# V-USB_Volume_Control_T2313_V1_1_60mm_x_6.net
KiCad netlist of a schematic drawn in EAGLE
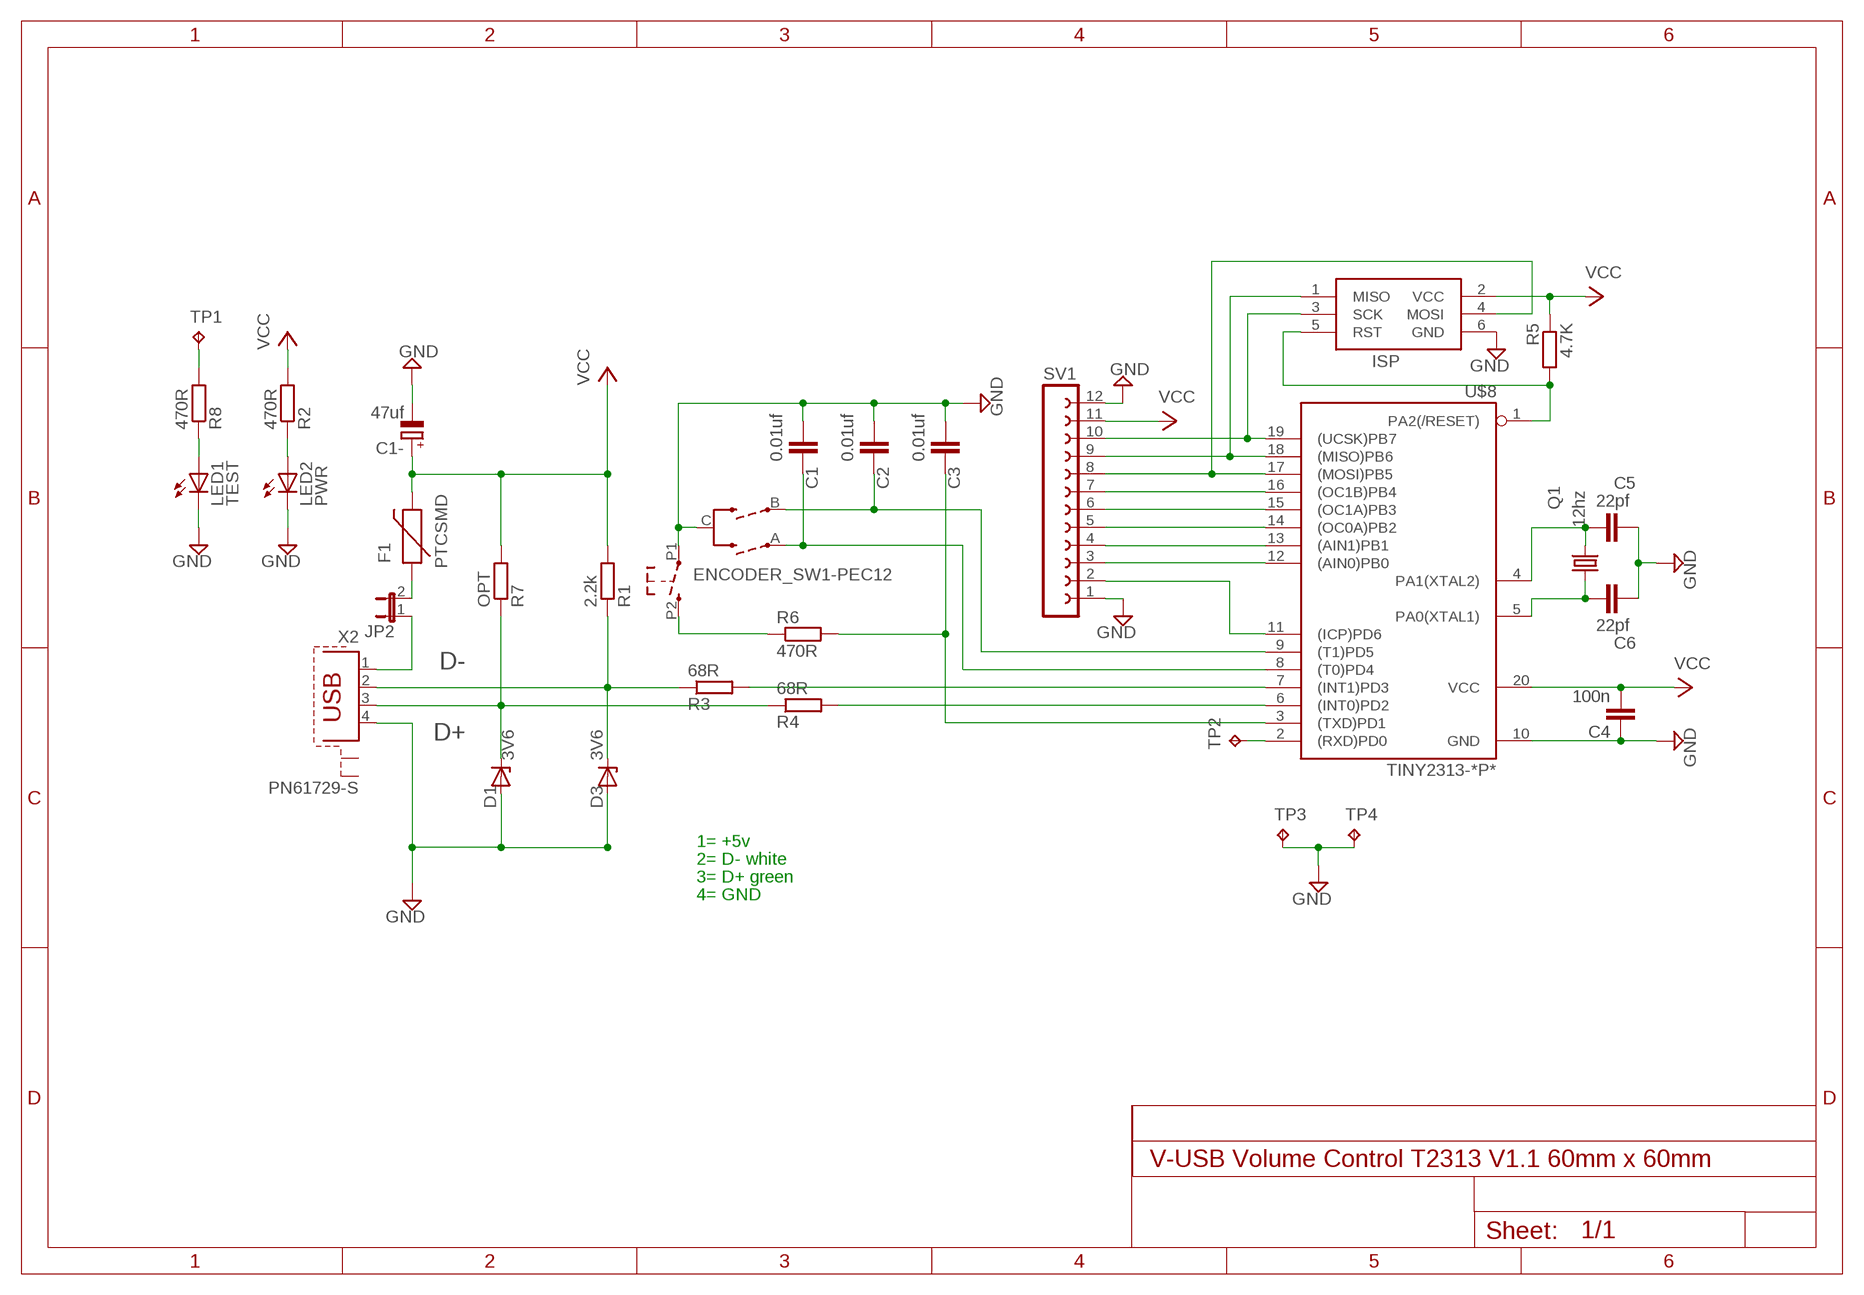
[diagram p0: schematic, sheet 1]

(export (version "E")
  (design (tool "Eeschema 10.0.6"))
  (components
    (comp (ref "C1")
      (value "0.01uf")
      (footprint "eagle-import:C5B2.5")
      (libsource (lib "eagle-import") (part "C5/2.5"))
    )
    (comp (ref "C1-")
      (value "47uf")
      (footprint "eagle-import:E2,5-6")
      (libsource (lib "eagle-import") (part "CPOL-EUE2.5-6"))
    )
    (comp (ref "C2")
      (value "0.01uf")
      (footprint "eagle-import:C5B2.5")
      (libsource (lib "eagle-import") (part "C5/2.5"))
    )
    (comp (ref "C3")
      (value "0.01uf")
      (footprint "eagle-import:C5B2.5")
      (libsource (lib "eagle-import") (part "C5/2.5"))
    )
    (comp (ref "C4")
      (value "100n")
      (footprint "eagle-import:C5B2.5")
      (libsource (lib "eagle-import") (part "C5/2.5"))
    )
    (comp (ref "C5")
      (value "22pf")
      (footprint "eagle-import:C2.5-2")
      (libsource (lib "eagle-import") (part "C2.5/2"))
    )
    (comp (ref "C6")
      (value "22pf")
      (footprint "eagle-import:C2.5-2")
      (libsource (lib "eagle-import") (part "C2.5/2"))
    )
    (comp (ref "D1")
      (value "3V6")
      (footprint "eagle-import:DO34Z7")
      (libsource (lib "eagle-import") (part "ZENER-DIODEDO34-7"))
    )
    (comp (ref "D3")
      (value "3V6")
      (footprint "eagle-import:DO34Z7")
      (libsource (lib "eagle-import") (part "ZENER-DIODEDO34-7"))
    )
    (comp (ref "F1")
      (value "PTCSMD")
      (footprint "eagle-import:PTC-1206")
      (libsource (lib "eagle-import") (part "PTCSMD"))
    )
    (comp (ref "ISP")
      (value "AVRISP-6")
      (footprint "eagle-import:AVRISP")
      (libsource (lib "eagle-import") (part "AVRISP-6"))
    )
    (comp (ref "JP2")
      (value "JP1E")
      (footprint "eagle-import:JP1")
      (libsource (lib "eagle-import") (part "JP1E"))
    )
    (comp (ref "LED1")
      (value "TEST")
      (footprint "eagle-import:LED3MM")
      (libsource (lib "eagle-import") (part "LED3MM"))
    )
    (comp (ref "LED2")
      (value "PWR")
      (footprint "eagle-import:LED3MM")
      (libsource (lib "eagle-import") (part "LED3MM"))
    )
    (comp (ref "Q1")
      (value "12hz")
      (footprint "eagle-import:HC49_S")
      (libsource (lib "eagle-import") (part "CRYSTALHC49S"))
    )
    (comp (ref "R1")
      (value "2.2k")
      (footprint "eagle-import:0207_10")
      (libsource (lib "eagle-import") (part "R-EU_0207/10"))
    )
    (comp (ref "R2")
      (value "470R")
      (footprint "eagle-import:0204_7")
      (libsource (lib "eagle-import") (part "R-EU_0204/7"))
    )
    (comp (ref "R3")
      (value "68R")
      (footprint "eagle-import:0207_10")
      (libsource (lib "eagle-import") (part "R-EU_0207/10"))
    )
    (comp (ref "R4")
      (value "68R")
      (footprint "eagle-import:0207_10")
      (libsource (lib "eagle-import") (part "R-EU_0207/10"))
    )
    (comp (ref "R5")
      (value "4.7K")
      (footprint "eagle-import:0204_7")
      (libsource (lib "eagle-import") (part "R-EU_0204/7"))
    )
    (comp (ref "R6")
      (value "470R")
      (footprint "eagle-import:0204_7")
      (libsource (lib "eagle-import") (part "R-EU_0204/7"))
    )
    (comp (ref "R7")
      (value "OPT")
      (footprint "eagle-import:0207_10")
      (libsource (lib "eagle-import") (part "R-EU_0207/10"))
    )
    (comp (ref "R8")
      (value "470R")
      (footprint "eagle-import:0207_10")
      (libsource (lib "eagle-import") (part "R-EU_0207/10"))
    )
    (comp (ref "SV1")
      (value "FE12-1")
      (footprint "eagle-import:FE12")
      (libsource (lib "eagle-import") (part "FE12-1"))
    )
    (comp (ref "SW3")
      (value "ENCODER_SW1-PEC12")
      (footprint "eagle-import:PEC12_INCREMENTAL_ENCODER")
      (libsource (lib "eagle-import") (part "ENCODER_SW1-PEC12"))
    )
    (comp (ref "TP1")
      (value "TPPAD1-13")
      (footprint "eagle-import:P1-13")
      (libsource (lib "eagle-import") (part "TPPAD1-13"))
    )
    (comp (ref "TP2")
      (value "TPPAD1-13")
      (footprint "eagle-import:P1-13")
      (libsource (lib "eagle-import") (part "TPPAD1-13"))
    )
    (comp (ref "TP3")
      (value "TPPAD1-20Y")
      (footprint "eagle-import:P1-20Y")
      (libsource (lib "eagle-import") (part "TPPAD1-20Y"))
    )
    (comp (ref "TP4")
      (value "TPPAD1-20Y")
      (footprint "eagle-import:P1-20Y")
      (libsource (lib "eagle-import") (part "TPPAD1-20Y"))
    )
    (comp (ref "U$8")
      (value "TINY2313-*P*")
      (footprint "eagle-import:DIL20")
      (libsource (lib "eagle-import") (part "TINY2313-P"))
    )
    (comp (ref "X2")
      (value "PN61729-S")
      (footprint "eagle-import:PN61729-S")
      (libsource (lib "eagle-import") (part "PN61729-S"))
    )
  )
  (nets
    (net (code "1") (name "/D+") (class "Default")
      (node (ref "D1") (pin "C") (pinfunction "C_C") (pintype "passive"))
      (node (ref "R4") (pin "1") (pinfunction "1_1") (pintype "passive"))
      (node (ref "R7") (pin "1") (pinfunction "1_1") (pintype "passive"))
      (node (ref "X2") (pin "3") (pinfunction "3_3") (pintype "passive"))
    )
    (net (code "2") (name "/D-") (class "Default")
      (node (ref "D3") (pin "C") (pinfunction "C_C") (pintype "passive"))
      (node (ref "R1") (pin "1") (pinfunction "1_1") (pintype "passive"))
      (node (ref "R3") (pin "1") (pinfunction "1_1") (pintype "passive"))
      (node (ref "X2") (pin "2") (pinfunction "2_2") (pintype "passive"))
    )
    (net (code "3") (name "GND") (class "Default")
      (node (ref "C1") (pin "1") (pinfunction "1_1") (pintype "passive"))
      (node (ref "C1-") (pin "-") (pinfunction "-_-") (pintype "passive"))
      (node (ref "C2") (pin "1") (pinfunction "1_1") (pintype "passive"))
      (node (ref "C3") (pin "1") (pinfunction "1_1") (pintype "passive"))
      (node (ref "C4") (pin "1") (pinfunction "1_1") (pintype "passive"))
      (node (ref "C5") (pin "2") (pinfunction "2_2") (pintype "passive"))
      (node (ref "C6") (pin "2") (pinfunction "2_2") (pintype "passive"))
      (node (ref "D1") (pin "A") (pinfunction "A_A") (pintype "passive"))
      (node (ref "D3") (pin "A") (pinfunction "A_A") (pintype "passive"))
      (node (ref "ISP") (pin "6") (pinfunction "GND_6") (pintype "power_in"))
      (node (ref "LED1") (pin "K") (pinfunction "C_K") (pintype "passive"))
      (node (ref "LED2") (pin "K") (pinfunction "C_K") (pintype "passive"))
      (node (ref "SV1") (pin "1") (pinfunction "1_1") (pintype "passive"))
      (node (ref "SV1") (pin "12") (pinfunction "12_12") (pintype "passive"))
      (node (ref "SW3") (pin "C") (pinfunction "C_C") (pintype "passive"))
      (node (ref "SW3") (pin "P1") (pinfunction "1_P1") (pintype "passive"))
      (node (ref "TP3") (pin "TP") (pinfunction "TP_TP") (pintype "input"))
      (node (ref "TP4") (pin "TP") (pinfunction "TP_TP") (pintype "input"))
      (node (ref "U$8") (pin "10") (pinfunction "GND_10") (pintype "power_in"))
      (node (ref "X2") (pin "4") (pinfunction "4_4") (pintype "passive"))
    )
    (net (code "4") (name "Net-(F1-Pad1)") (class "Default")
      (node (ref "F1") (pin "1") (pinfunction "1_1") (pintype "bidirectional"))
      (node (ref "JP2") (pin "2") (pinfunction "2_2") (pintype "passive"))
    )
    (net (code "5") (name "Net-(ISP-MISO)") (class "Default")
      (node (ref "ISP") (pin "1") (pinfunction "MISO_1") (pintype "input"))
      (node (ref "SV1") (pin "9") (pinfunction "9_9") (pintype "passive"))
      (node (ref "U$8") (pin "18") (pinfunction "(MISO)PB6_18") (pintype "bidirectional"))
    )
    (net (code "6") (name "Net-(ISP-MOSI)") (class "Default")
      (node (ref "ISP") (pin "4") (pinfunction "MOSI_4") (pintype "output"))
      (node (ref "SV1") (pin "8") (pinfunction "8_8") (pintype "passive"))
      (node (ref "U$8") (pin "17") (pinfunction "(MOSI)PB5_17") (pintype "bidirectional"))
    )
    (net (code "7") (name "Net-(ISP-RST)") (class "Default")
      (node (ref "ISP") (pin "5") (pinfunction "RST_5") (pintype "output"))
      (node (ref "R5") (pin "2") (pinfunction "2_2") (pintype "passive"))
      (node (ref "U$8") (pin "1") (pinfunction "PA2(/RESET)_1") (pintype "input"))
    )
    (net (code "8") (name "Net-(ISP-SCK)") (class "Default")
      (node (ref "ISP") (pin "3") (pinfunction "SCK_3") (pintype "output"))
      (node (ref "SV1") (pin "10") (pinfunction "10_10") (pintype "passive"))
      (node (ref "U$8") (pin "19") (pinfunction "(UCSK)PB7_19") (pintype "bidirectional"))
    )
    (net (code "9") (name "Net-(JP2-Pad1)") (class "Default")
      (node (ref "JP2") (pin "1") (pinfunction "1_1") (pintype "passive"))
      (node (ref "X2") (pin "1") (pinfunction "1_1") (pintype "passive"))
    )
    (net (code "10") (name "Net-(LED1-PadA)") (class "Default")
      (node (ref "LED1") (pin "A") (pinfunction "A_A") (pintype "passive"))
      (node (ref "R8") (pin "1") (pinfunction "1_1") (pintype "passive"))
    )
    (net (code "11") (name "Net-(LED2-PadA)") (class "Default")
      (node (ref "LED2") (pin "A") (pinfunction "A_A") (pintype "passive"))
      (node (ref "R2") (pin "1") (pinfunction "1_1") (pintype "passive"))
    )
    (net (code "12") (name "Net-(R8-Pad2)") (class "Default")
      (node (ref "R8") (pin "2") (pinfunction "2_2") (pintype "passive"))
      (node (ref "TP1") (pin "TP") (pinfunction "TP_TP") (pintype "input"))
    )
    (net (code "13") (name "Net-(SW3B-2)") (class "Default")
      (node (ref "R6") (pin "1") (pinfunction "1_1") (pintype "passive"))
      (node (ref "SW3") (pin "P2") (pinfunction "2_P2") (pintype "passive"))
    )
    (net (code "14") (name "Net-(U$8-(AIN0)PB0)") (class "Default")
      (node (ref "SV1") (pin "3") (pinfunction "3_3") (pintype "passive"))
      (node (ref "U$8") (pin "12") (pinfunction "(AIN0)PB0_12") (pintype "bidirectional"))
    )
    (net (code "15") (name "Net-(U$8-(AIN1)PB1)") (class "Default")
      (node (ref "SV1") (pin "4") (pinfunction "4_4") (pintype "passive"))
      (node (ref "U$8") (pin "13") (pinfunction "(AIN1)PB1_13") (pintype "bidirectional"))
    )
    (net (code "16") (name "Net-(U$8-(ICP)PD6)") (class "Default")
      (node (ref "SV1") (pin "2") (pinfunction "2_2") (pintype "passive"))
      (node (ref "U$8") (pin "11") (pinfunction "(ICP)PD6_11") (pintype "bidirectional"))
    )
    (net (code "17") (name "Net-(U$8-(INT0)PD2)") (class "Default")
      (node (ref "R4") (pin "2") (pinfunction "2_2") (pintype "passive"))
      (node (ref "U$8") (pin "6") (pinfunction "(INT0)PD2_6") (pintype "bidirectional"))
    )
    (net (code "18") (name "Net-(U$8-(INT1)PD3)") (class "Default")
      (node (ref "R3") (pin "2") (pinfunction "2_2") (pintype "passive"))
      (node (ref "U$8") (pin "7") (pinfunction "(INT1)PD3_7") (pintype "bidirectional"))
    )
    (net (code "19") (name "Net-(U$8-(OC0A)PB2)") (class "Default")
      (node (ref "SV1") (pin "5") (pinfunction "5_5") (pintype "passive"))
      (node (ref "U$8") (pin "14") (pinfunction "(OC0A)PB2_14") (pintype "bidirectional"))
    )
    (net (code "20") (name "Net-(U$8-(OC1A)PB3)") (class "Default")
      (node (ref "SV1") (pin "6") (pinfunction "6_6") (pintype "passive"))
      (node (ref "U$8") (pin "15") (pinfunction "(OC1A)PB3_15") (pintype "bidirectional"))
    )
    (net (code "21") (name "Net-(U$8-(OC1B)PB4)") (class "Default")
      (node (ref "SV1") (pin "7") (pinfunction "7_7") (pintype "passive"))
      (node (ref "U$8") (pin "16") (pinfunction "(OC1B)PB4_16") (pintype "bidirectional"))
    )
    (net (code "22") (name "Net-(U$8-(RXD)PD0)") (class "Default")
      (node (ref "TP2") (pin "TP") (pinfunction "TP_TP") (pintype "input"))
      (node (ref "U$8") (pin "2") (pinfunction "(RXD)PD0_2") (pintype "bidirectional"))
    )
    (net (code "23") (name "Net-(U$8-(T0)PD4)") (class "Default")
      (node (ref "C1") (pin "2") (pinfunction "2_2") (pintype "passive"))
      (node (ref "SW3") (pin "A") (pinfunction "A_A") (pintype "passive"))
      (node (ref "U$8") (pin "8") (pinfunction "(T0)PD4_8") (pintype "bidirectional"))
    )
    (net (code "24") (name "Net-(U$8-(T1)PD5)") (class "Default")
      (node (ref "C2") (pin "2") (pinfunction "2_2") (pintype "passive"))
      (node (ref "SW3") (pin "B") (pinfunction "B_B") (pintype "passive"))
      (node (ref "U$8") (pin "9") (pinfunction "(T1)PD5_9") (pintype "bidirectional"))
    )
    (net (code "25") (name "Net-(U$8-(TXD)PD1)") (class "Default")
      (node (ref "C3") (pin "2") (pinfunction "2_2") (pintype "passive"))
      (node (ref "R6") (pin "2") (pinfunction "2_2") (pintype "passive"))
      (node (ref "U$8") (pin "3") (pinfunction "(TXD)PD1_3") (pintype "bidirectional"))
    )
    (net (code "26") (name "Net-(U$8-PA0(XTAL1))") (class "Default")
      (node (ref "C6") (pin "1") (pinfunction "1_1") (pintype "passive"))
      (node (ref "Q1") (pin "1") (pinfunction "1_1") (pintype "passive"))
      (node (ref "U$8") (pin "5") (pinfunction "PA0(XTAL1)_5") (pintype "bidirectional"))
    )
    (net (code "27") (name "Net-(U$8-PA1(XTAL2))") (class "Default")
      (node (ref "C5") (pin "1") (pinfunction "1_1") (pintype "passive"))
      (node (ref "Q1") (pin "2") (pinfunction "2_2") (pintype "passive"))
      (node (ref "U$8") (pin "4") (pinfunction "PA1(XTAL2)_4") (pintype "bidirectional"))
    )
    (net (code "28") (name "VCC") (class "Default")
      (node (ref "C1-") (pin "+") (pinfunction "+_+") (pintype "passive"))
      (node (ref "C4") (pin "2") (pinfunction "2_2") (pintype "passive"))
      (node (ref "F1") (pin "2") (pinfunction "2_2") (pintype "bidirectional"))
      (node (ref "ISP") (pin "2") (pinfunction "VCC_2") (pintype "power_in"))
      (node (ref "R1") (pin "2") (pinfunction "2_2") (pintype "passive"))
      (node (ref "R2") (pin "2") (pinfunction "2_2") (pintype "passive"))
      (node (ref "R5") (pin "1") (pinfunction "1_1") (pintype "passive"))
      (node (ref "R7") (pin "2") (pinfunction "2_2") (pintype "passive"))
      (node (ref "SV1") (pin "11") (pinfunction "11_11") (pintype "passive"))
      (node (ref "U$8") (pin "20") (pinfunction "VCC_20") (pintype "power_in"))
    )
    (net (code "29") (name "unconnected-(X2-PadS1)") (class "Default")
      (node (ref "X2") (pin "S1") (pinfunction "S1_S1") (pintype "passive"))
    )
    (net (code "30") (name "unconnected-(X2-PadS2)") (class "Default")
      (node (ref "X2") (pin "S2") (pinfunction "S2_S2") (pintype "passive"))
    )
  )
)
